# Power_2.net
KiCad netlist of a schematic drawn in Altium Designer
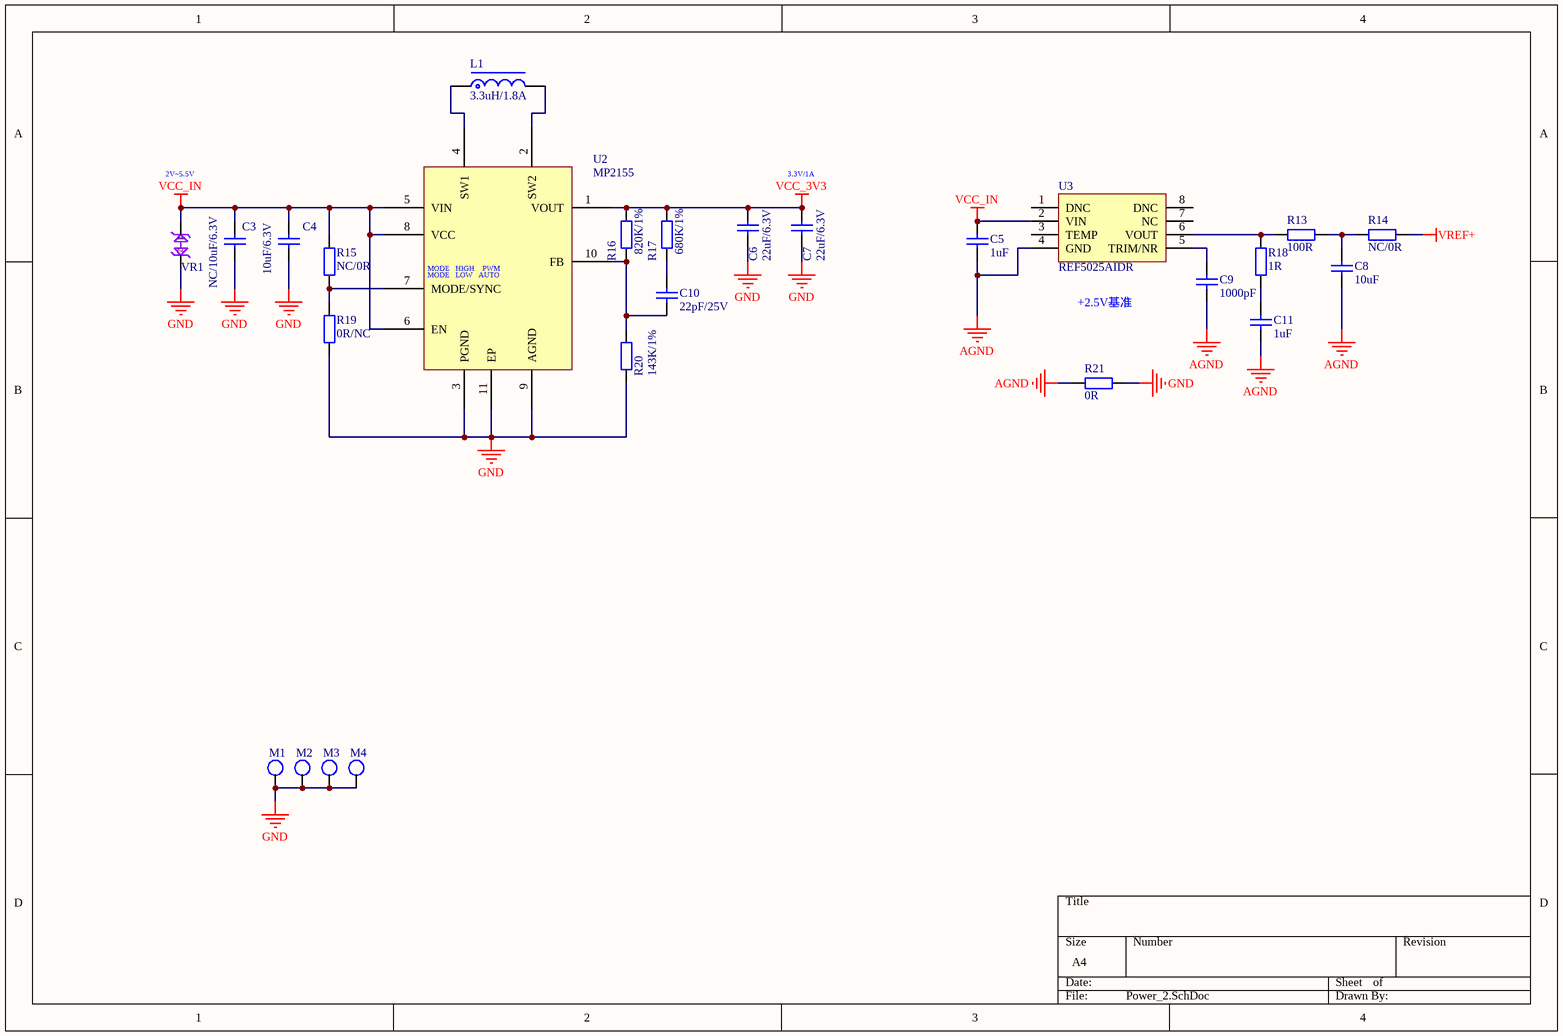
[diagram p0: Power_2.SchDoc]

(export (version "E")
  (design (tool "Eeschema 10.0.6"))
  (components
    (comp (ref "C3")
      (value "NC/10uF/6.3V")
      (footprint "C0603_L")
      (description "贴片电容")
      (libsource (lib "0.1 - 电阻-电容-电感-晶振-晶体-磁珠-电位器") (part "C"))
    )
    (comp (ref "C4")
      (value "10uF/6.3V")
      (footprint "C0603_L")
      (description "贴片电容")
      (libsource (lib "0.1 - 电阻-电容-电感-晶振-晶体-磁珠-电位器") (part "C"))
    )
    (comp (ref "C5")
      (value "1uF")
      (footprint "C0402_L")
      (description "贴片电容")
      (libsource (lib "0.1 - 电阻-电容-电感-晶振-晶体-磁珠-电位器") (part "C"))
    )
    (comp (ref "C6")
      (value "22uF/6.3V")
      (footprint "C0603_L")
      (description "贴片电容")
      (libsource (lib "0.1 - 电阻-电容-电感-晶振-晶体-磁珠-电位器") (part "C"))
    )
    (comp (ref "C7")
      (value "22uF/6.3V")
      (footprint "C0603_L")
      (description "贴片电容")
      (libsource (lib "0.1 - 电阻-电容-电感-晶振-晶体-磁珠-电位器") (part "C"))
    )
    (comp (ref "C8")
      (value "10uF")
      (footprint "C0603_L")
      (description "贴片电容")
      (libsource (lib "0.1 - 电阻-电容-电感-晶振-晶体-磁珠-电位器") (part "C"))
    )
    (comp (ref "C9")
      (value "1000pF")
      (footprint "C0402_L")
      (description "贴片电容")
      (libsource (lib "0.1 - 电阻-电容-电感-晶振-晶体-磁珠-电位器") (part "C"))
    )
    (comp (ref "C10")
      (value "22pF/25V")
      (footprint "C0402_L")
      (description "贴片电容")
      (libsource (lib "0.1 - 电阻-电容-电感-晶振-晶体-磁珠-电位器") (part "C"))
    )
    (comp (ref "C11")
      (value "1uF")
      (footprint "C0402_L")
      (description "贴片电容")
      (libsource (lib "0.1 - 电阻-电容-电感-晶振-晶体-磁珠-电位器") (part "C"))
    )
    (comp (ref "L1")
      (value "3.3uH/1.8A")
      (footprint "NR2520")
      (description "太诱-NR磁胶电感")
      (libsource (lib "0.1 - 电阻-电容-电感-晶振-晶体-磁珠-电位器") (part "L-NR"))
    )
    (comp (ref "M1")
      (value "M2")
      (footprint "M2")
      (description "M2孔支撑柱")
      (libsource (lib "USER_Lib") (part "M2系列"))
    )
    (comp (ref "M2")
      (value "M2")
      (footprint "M2")
      (description "M2孔支撑柱")
      (libsource (lib "USER_Lib") (part "M2系列"))
    )
    (comp (ref "M3")
      (value "M2")
      (footprint "M2")
      (description "M2孔支撑柱")
      (libsource (lib "USER_Lib") (part "M2系列"))
    )
    (comp (ref "M4")
      (value "M2")
      (footprint "M2")
      (description "M2孔支撑柱")
      (libsource (lib "USER_Lib") (part "M2系列"))
    )
    (comp (ref "R13")
      (value "100R")
      (footprint "R0402_L")
      (description "贴片电阻")
      (libsource (lib "0.1 - 电阻-电容-电感-晶振-晶体-磁珠-电位器") (part "R"))
    )
    (comp (ref "R14")
      (value "NC/0R")
      (footprint "R0402_L")
      (description "贴片电阻")
      (libsource (lib "0.1 - 电阻-电容-电感-晶振-晶体-磁珠-电位器") (part "R"))
    )
    (comp (ref "R15")
      (value "NC/0R")
      (footprint "R0402_L")
      (description "贴片电阻")
      (libsource (lib "0.1 - 电阻-电容-电感-晶振-晶体-磁珠-电位器") (part "R"))
    )
    (comp (ref "R16")
      (value "820K/1%")
      (footprint "R0402_L")
      (description "贴片电阻")
      (libsource (lib "0.1 - 电阻-电容-电感-晶振-晶体-磁珠-电位器") (part "R"))
    )
    (comp (ref "R17")
      (value "680K/1%")
      (footprint "R0402_L")
      (description "贴片电阻")
      (libsource (lib "0.1 - 电阻-电容-电感-晶振-晶体-磁珠-电位器") (part "R"))
    )
    (comp (ref "R18")
      (value "1R")
      (footprint "R0402_L")
      (description "贴片电阻")
      (libsource (lib "0.1 - 电阻-电容-电感-晶振-晶体-磁珠-电位器") (part "R"))
    )
    (comp (ref "R19")
      (value "0R/NC")
      (footprint "R0402_L")
      (description "贴片电阻")
      (libsource (lib "0.1 - 电阻-电容-电感-晶振-晶体-磁珠-电位器") (part "R"))
    )
    (comp (ref "R20")
      (value "143K/1%")
      (footprint "R0402_L")
      (description "贴片电阻")
      (libsource (lib "0.1 - 电阻-电容-电感-晶振-晶体-磁珠-电位器") (part "R"))
    )
    (comp (ref "R21")
      (value "0R")
      (footprint "R0402_L")
      (description "贴片电阻")
      (libsource (lib "0.1 - 电阻-电容-电感-晶振-晶体-磁珠-电位器") (part "R"))
    )
    (comp (ref "U2")
      (value "MP2155")
      (footprint "QFN10(3mmX3mm)")
      (description "高效、低静态电流的Buck-Boost变换器")
      (libsource (lib "USER_Lib") (part "MP2155"))
    )
    (comp (ref "U3")
      (value "REF5025AIDR")
      (footprint "SOIC-8L")
      (description "3uVpp/V噪声 3ppm/℃漂移 电压基准 0.05%")
      (libsource (lib "USER_Lib") (part "REF5025AIDR"))
    )
    (comp (ref "VR1")
      (value "UAD8C05L01")
      (footprint "SOD882")
      (libsource (lib "USER_Lib") (part "UAD8C05L01"))
    )
  )
  (nets
    (net (code "1") (name "AGND") (class "Default")
      (node (ref "C11") (pin "1") (pinfunction "1_1") (pintype "passive"))
      (node (ref "C5") (pin "1") (pinfunction "1_1") (pintype "passive"))
      (node (ref "C8") (pin "1") (pinfunction "1_1") (pintype "passive"))
      (node (ref "C9") (pin "1") (pinfunction "1_1") (pintype "passive"))
      (node (ref "R21") (pin "1") (pinfunction "1_1") (pintype "passive"))
      (node (ref "U3") (pin "4") (pinfunction "GND_4") (pintype "passive"))
    )
    (net (code "2") (name "GND") (class "Default")
      (node (ref "C3") (pin "1") (pinfunction "1_1") (pintype "passive"))
      (node (ref "C4") (pin "1") (pinfunction "1_1") (pintype "passive"))
      (node (ref "C6") (pin "1") (pinfunction "1_1") (pintype "passive"))
      (node (ref "C7") (pin "1") (pinfunction "1_1") (pintype "passive"))
      (node (ref "M1") (pin "1") (pinfunction "1_1") (pintype "passive"))
      (node (ref "M2") (pin "1") (pinfunction "1_1") (pintype "passive"))
      (node (ref "M3") (pin "1") (pinfunction "1_1") (pintype "passive"))
      (node (ref "M4") (pin "1") (pinfunction "1_1") (pintype "passive"))
      (node (ref "R19") (pin "1") (pinfunction "1_1") (pintype "passive"))
      (node (ref "R20") (pin "1") (pinfunction "1_1") (pintype "passive"))
      (node (ref "R21") (pin "2") (pinfunction "2_2") (pintype "passive"))
      (node (ref "U2") (pin "11") (pinfunction "EP_11") (pintype "passive"))
      (node (ref "U2") (pin "3") (pinfunction "PGND_3") (pintype "passive"))
      (node (ref "U2") (pin "9") (pinfunction "AGND_9") (pintype "passive"))
      (node (ref "VR1") (pin "2") (pinfunction "2_2") (pintype "passive"))
    )
    (net (code "3") (name "Net-(C8-Pad2)") (class "Default")
      (node (ref "C8") (pin "2") (pinfunction "2_2") (pintype "passive"))
      (node (ref "R13") (pin "2") (pinfunction "2_2") (pintype "passive"))
      (node (ref "R14") (pin "1") (pinfunction "1_1") (pintype "passive"))
    )
    (net (code "4") (name "Net-(C10-Pad2)") (class "Default")
      (node (ref "C10") (pin "2") (pinfunction "2_2") (pintype "passive"))
      (node (ref "R17") (pin "1") (pinfunction "1_1") (pintype "passive"))
    )
    (net (code "5") (name "Net-(C11-Pad2)") (class "Default")
      (node (ref "C11") (pin "2") (pinfunction "2_2") (pintype "passive"))
      (node (ref "R18") (pin "1") (pinfunction "1_1") (pintype "passive"))
    )
    (net (code "6") (name "Net-(U2-FB)") (class "Default")
      (node (ref "C10") (pin "1") (pinfunction "1_1") (pintype "passive"))
      (node (ref "R16") (pin "1") (pinfunction "1_1") (pintype "passive"))
      (node (ref "R20") (pin "2") (pinfunction "2_2") (pintype "passive"))
      (node (ref "U2") (pin "10") (pinfunction "FB_10") (pintype "passive"))
    )
    (net (code "7") (name "Net-(U2-MODE{slash}SYNC)") (class "Default")
      (node (ref "R15") (pin "1") (pinfunction "1_1") (pintype "passive"))
      (node (ref "R19") (pin "2") (pinfunction "2_2") (pintype "passive"))
      (node (ref "U2") (pin "7") (pinfunction "MODE/SYNC_7") (pintype "passive"))
    )
    (net (code "8") (name "Net-(U2-SW1)") (class "Default")
      (node (ref "L1") (pin "1") (pinfunction "1_1") (pintype "passive"))
      (node (ref "U2") (pin "4") (pinfunction "SW1_4") (pintype "passive"))
    )
    (net (code "9") (name "Net-(U2-SW2)") (class "Default")
      (node (ref "L1") (pin "2") (pinfunction "2_2") (pintype "passive"))
      (node (ref "U2") (pin "2") (pinfunction "SW2_2") (pintype "passive"))
    )
    (net (code "10") (name "Net-(U3-TRIM{slash}NR)") (class "Default")
      (node (ref "C9") (pin "2") (pinfunction "2_2") (pintype "passive"))
      (node (ref "U3") (pin "5") (pinfunction "TRIM/NR_5") (pintype "passive"))
    )
    (net (code "11") (name "Net-(U3-VOUT)") (class "Default")
      (node (ref "R13") (pin "1") (pinfunction "1_1") (pintype "passive"))
      (node (ref "R18") (pin "2") (pinfunction "2_2") (pintype "passive"))
      (node (ref "U3") (pin "6") (pinfunction "VOUT_6") (pintype "passive"))
    )
    (net (code "12") (name "VCC_3V3") (class "Default")
      (node (ref "C6") (pin "2") (pinfunction "2_2") (pintype "passive"))
      (node (ref "C7") (pin "2") (pinfunction "2_2") (pintype "passive"))
      (node (ref "R16") (pin "2") (pinfunction "2_2") (pintype "passive"))
      (node (ref "R17") (pin "2") (pinfunction "2_2") (pintype "passive"))
      (node (ref "U2") (pin "1") (pinfunction "VOUT_1") (pintype "passive"))
    )
    (net (code "13") (name "VCC_IN") (class "Default")
      (node (ref "C3") (pin "2") (pinfunction "2_2") (pintype "passive"))
      (node (ref "C4") (pin "2") (pinfunction "2_2") (pintype "passive"))
      (node (ref "C5") (pin "2") (pinfunction "2_2") (pintype "passive"))
      (node (ref "R15") (pin "2") (pinfunction "2_2") (pintype "passive"))
      (node (ref "U2") (pin "5") (pinfunction "VIN_5") (pintype "passive"))
      (node (ref "U2") (pin "6") (pinfunction "EN_6") (pintype "passive"))
      (node (ref "U2") (pin "8") (pinfunction "VCC_8") (pintype "passive"))
      (node (ref "U3") (pin "2") (pinfunction "VIN_2") (pintype "passive"))
      (node (ref "VR1") (pin "1") (pinfunction "1_1") (pintype "passive"))
    )
    (net (code "14") (name "VREF+") (class "Default")
      (node (ref "R14") (pin "2") (pinfunction "2_2") (pintype "passive"))
    )
    (net (code "15") (name "unconnected-(U3-DNC-Pad1)") (class "Default")
      (node (ref "U3") (pin "1") (pinfunction "DNC_1") (pintype "passive"))
    )
    (net (code "16") (name "unconnected-(U3-DNC-Pad8)") (class "Default")
      (node (ref "U3") (pin "8") (pinfunction "DNC_8") (pintype "passive"))
    )
    (net (code "17") (name "unconnected-(U3-NC-Pad7)") (class "Default")
      (node (ref "U3") (pin "7") (pinfunction "NC_7") (pintype "passive"))
    )
    (net (code "18") (name "unconnected-(U3-TEMP-Pad3)") (class "Default")
      (node (ref "U3") (pin "3") (pinfunction "TEMP_3") (pintype "passive"))
    )
  )
)
